# led1.net
KiCad netlist of a schematic drawn in Altium Designer
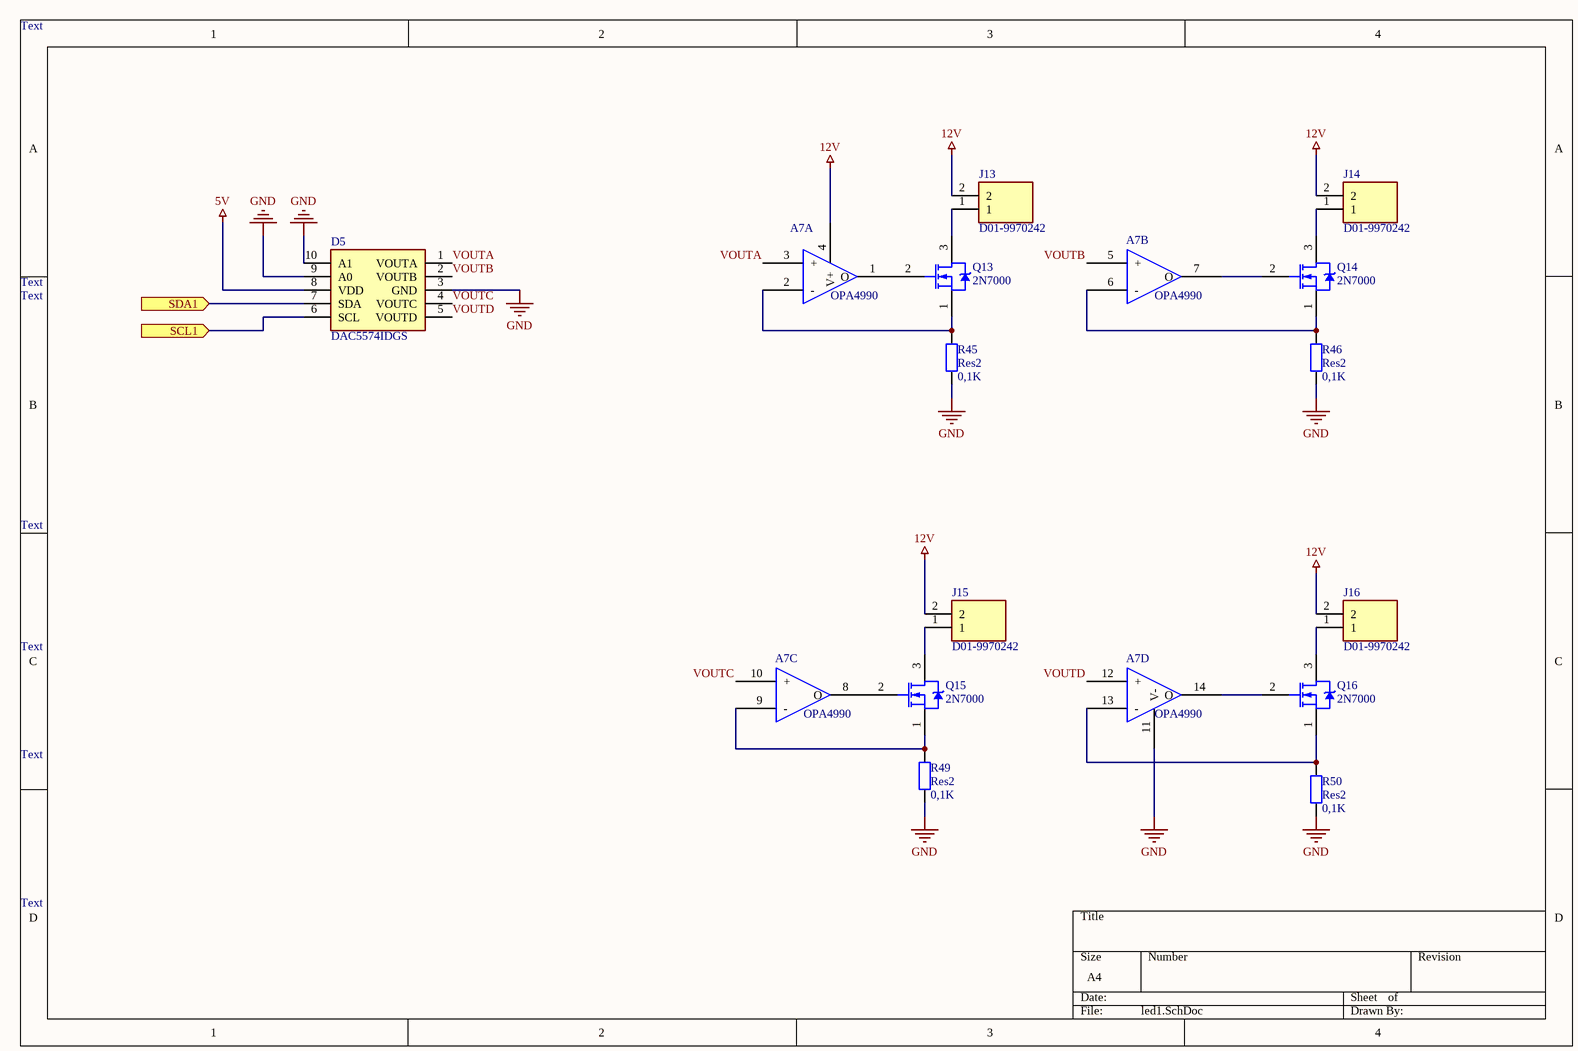
[diagram p0: led1.SchDoc]

(export (version "E")
  (design (tool "Eeschema 10.0.6"))
  (components
    (comp (ref "A7")
      (value "OPA4990")
      (footprint "SOIC127P600X175-14N")
      (libsource (lib "Kalibracija") (part "OPA4990"))
    )
    (comp (ref "D5")
      (value "DAC5574IDGS")
      (footprint "SOP50P490X110-10N")
      (description "Integrated Circuit")
      (fields
        (field (name "MOUSER PART NUMBER") "595-DAC5574IDGS")
        (field (name "RS PART NUMBER") "6621533P")
      )
      (libsource (lib "*") (part "DAC5574IDGS"))
    )
    (comp (ref "J13")
      (value "D01-9970242")
      (footprint "HDR1X2")
      (description "Connector")
      (fields (field (name "MOUSER PART NUMBER") "855-D01-9970242"))
      (libsource (lib "SamacSys2") (part "D01-9970242"))
    )
    (comp (ref "J14")
      (value "D01-9970242")
      (footprint "HDR1X2")
      (description "Connector")
      (fields (field (name "MOUSER PART NUMBER") "855-D01-9970242"))
      (libsource (lib "SamacSys2") (part "D01-9970242"))
    )
    (comp (ref "J15")
      (value "D01-9970242")
      (footprint "HDR1X2")
      (description "Connector")
      (fields (field (name "MOUSER PART NUMBER") "855-D01-9970242"))
      (libsource (lib "SamacSys2") (part "D01-9970242"))
    )
    (comp (ref "J16")
      (value "D01-9970242")
      (footprint "HDR1X2")
      (description "Connector")
      (fields (field (name "MOUSER PART NUMBER") "855-D01-9970242"))
      (libsource (lib "SamacSys2") (part "D01-9970242"))
    )
    (comp (ref "Q13")
      (value "2N7000")
      (footprint "ONSC-TO-92-3-29-11")
      (description "Small Signal MOSFET, 200 mA, 60 V, N-Channel, 3-Pin TO-92, Bulk Box")
      (fields (field (name "MANUFACTURER") "On Semiconductor"))
      (libsource (lib "Components - 24.04.20 - 07.58") (part "CMP-1058-00936-1"))
    )
    (comp (ref "Q14")
      (value "2N7000")
      (footprint "ONSC-TO-92-3-29-11")
      (description "Small Signal MOSFET, 200 mA, 60 V, N-Channel, 3-Pin TO-92, Bulk Box")
      (fields (field (name "MANUFACTURER") "On Semiconductor"))
      (libsource (lib "Components - 24.04.20 - 07.58") (part "CMP-1058-00936-1"))
    )
    (comp (ref "Q15")
      (value "2N7000")
      (footprint "ONSC-TO-92-3-29-11")
      (description "Small Signal MOSFET, 200 mA, 60 V, N-Channel, 3-Pin TO-92, Bulk Box")
      (fields (field (name "MANUFACTURER") "On Semiconductor"))
      (libsource (lib "Components - 24.04.20 - 07.58") (part "CMP-1058-00936-1"))
    )
    (comp (ref "Q16")
      (value "2N7000")
      (footprint "ONSC-TO-92-3-29-11")
      (description "Small Signal MOSFET, 200 mA, 60 V, N-Channel, 3-Pin TO-92, Bulk Box")
      (fields (field (name "MANUFACTURER") "On Semiconductor"))
      (libsource (lib "Components - 24.04.20 - 07.58") (part "CMP-1058-00936-1"))
    )
    (comp (ref "R45")
      (value "Res2")
      (footprint "C1210")
      (description "Resistor")
      (fields (field (name "ALTIUM_VALUE") "0,1K") (field (name "PUBLISHER") "Altium Limited"))
      (libsource (lib "Miscellaneous Devices") (part "Res2"))
    )
    (comp (ref "R46")
      (value "Res2")
      (footprint "C1210")
      (description "Resistor")
      (fields (field (name "ALTIUM_VALUE") "0,1K") (field (name "PUBLISHER") "Altium Limited"))
      (libsource (lib "Miscellaneous Devices") (part "Res2"))
    )
    (comp (ref "R49")
      (value "Res2")
      (footprint "C1210")
      (description "Resistor")
      (fields (field (name "ALTIUM_VALUE") "0,1K") (field (name "PUBLISHER") "Altium Limited"))
      (libsource (lib "") (part "Res2_1"))
    )
    (comp (ref "R50")
      (value "Res2")
      (footprint "C1210")
      (description "Resistor")
      (fields (field (name "ALTIUM_VALUE") "0,1K") (field (name "PUBLISHER") "Altium Limited"))
      (libsource (lib "") (part "Res2_1"))
    )
  )
  (nets
    (net (code "1") (name "/SCL1") (class "Default")
      (node (ref "D5") (pin "6") (pinfunction "SCL_6") (pintype "passive"))
    )
    (net (code "2") (name "/SDA1") (class "Default")
      (node (ref "D5") (pin "7") (pinfunction "SDA_7") (pintype "passive"))
    )
    (net (code "3") (name "/VOUTA") (class "Default")
      (node (ref "A7") (pin "3") (pinfunction "+_3") (pintype "passive"))
      (node (ref "D5") (pin "1") (pinfunction "VOUTA_1") (pintype "passive"))
    )
    (net (code "4") (name "/VOUTB") (class "Default")
      (node (ref "A7") (pin "5") (pinfunction "+_5") (pintype "passive"))
      (node (ref "D5") (pin "2") (pinfunction "VOUTB_2") (pintype "passive"))
    )
    (net (code "5") (name "/VOUTC") (class "Default")
      (node (ref "A7") (pin "10") (pinfunction "+_10") (pintype "passive"))
      (node (ref "D5") (pin "4") (pinfunction "VOUTC_4") (pintype "passive"))
    )
    (net (code "6") (name "/VOUTD") (class "Default")
      (node (ref "A7") (pin "12") (pinfunction "+_12") (pintype "passive"))
      (node (ref "D5") (pin "5") (pinfunction "VOUTD_5") (pintype "passive"))
    )
    (net (code "7") (name "5V") (class "Default")
      (node (ref "D5") (pin "8") (pinfunction "VDD_8") (pintype "passive"))
    )
    (net (code "8") (name "12V") (class "Default")
      (node (ref "A7") (pin "4") (pinfunction "V+_4") (pintype "power_in"))
      (node (ref "J13") (pin "2") (pinfunction "2_2") (pintype "passive"))
      (node (ref "J14") (pin "2") (pinfunction "2_2") (pintype "passive"))
      (node (ref "J15") (pin "2") (pinfunction "2_2") (pintype "passive"))
      (node (ref "J16") (pin "2") (pinfunction "2_2") (pintype "passive"))
    )
    (net (code "9") (name "GND") (class "Default")
      (node (ref "A7") (pin "11") (pinfunction "V-_11") (pintype "power_in"))
      (node (ref "D5") (pin "10") (pinfunction "A1_10") (pintype "passive"))
      (node (ref "D5") (pin "3") (pinfunction "GND_3") (pintype "passive"))
      (node (ref "D5") (pin "9") (pinfunction "A0_9") (pintype "passive"))
      (node (ref "R45") (pin "1") (pinfunction "1_1") (pintype "passive"))
      (node (ref "R46") (pin "1") (pinfunction "1_1") (pintype "passive"))
      (node (ref "R49") (pin "2") (pinfunction "2_2") (pintype "passive"))
      (node (ref "R50") (pin "2") (pinfunction "2_2") (pintype "passive"))
    )
    (net (code "10") (name "Net-(A7A--)") (class "Default")
      (node (ref "A7") (pin "2") (pinfunction "-_2") (pintype "passive"))
      (node (ref "Q13") (pin "1") (pinfunction "S_1") (pintype "passive"))
      (node (ref "R45") (pin "2") (pinfunction "2_2") (pintype "passive"))
    )
    (net (code "11") (name "Net-(A7A-O)") (class "Default")
      (node (ref "A7") (pin "1") (pinfunction "O_1") (pintype "passive"))
      (node (ref "Q13") (pin "2") (pinfunction "G_2") (pintype "passive"))
    )
    (net (code "12") (name "Net-(A7B--)") (class "Default")
      (node (ref "A7") (pin "6") (pinfunction "-_6") (pintype "passive"))
      (node (ref "Q14") (pin "1") (pinfunction "S_1") (pintype "passive"))
      (node (ref "R46") (pin "2") (pinfunction "2_2") (pintype "passive"))
    )
    (net (code "13") (name "Net-(A7B-O)") (class "Default")
      (node (ref "A7") (pin "7") (pinfunction "O_7") (pintype "passive"))
      (node (ref "Q14") (pin "2") (pinfunction "G_2") (pintype "passive"))
    )
    (net (code "14") (name "Net-(A7C--)") (class "Default")
      (node (ref "A7") (pin "9") (pinfunction "-_9") (pintype "passive"))
      (node (ref "Q15") (pin "1") (pinfunction "S_1") (pintype "passive"))
      (node (ref "R49") (pin "1") (pinfunction "1_1") (pintype "passive"))
    )
    (net (code "15") (name "Net-(A7C-O)") (class "Default")
      (node (ref "A7") (pin "8") (pinfunction "O_8") (pintype "passive"))
      (node (ref "Q15") (pin "2") (pinfunction "G_2") (pintype "passive"))
    )
    (net (code "16") (name "Net-(A7D--)") (class "Default")
      (node (ref "A7") (pin "13") (pinfunction "-_13") (pintype "passive"))
      (node (ref "Q16") (pin "1") (pinfunction "S_1") (pintype "passive"))
      (node (ref "R50") (pin "1") (pinfunction "1_1") (pintype "passive"))
    )
    (net (code "17") (name "Net-(A7D-O)") (class "Default")
      (node (ref "A7") (pin "14") (pinfunction "O_14") (pintype "passive"))
      (node (ref "Q16") (pin "2") (pinfunction "G_2") (pintype "passive"))
    )
    (net (code "18") (name "Net-(Q13-D)") (class "Default")
      (node (ref "J13") (pin "1") (pinfunction "1_1") (pintype "passive"))
      (node (ref "Q13") (pin "3") (pinfunction "D_3") (pintype "passive"))
    )
    (net (code "19") (name "Net-(Q14-D)") (class "Default")
      (node (ref "J14") (pin "1") (pinfunction "1_1") (pintype "passive"))
      (node (ref "Q14") (pin "3") (pinfunction "D_3") (pintype "passive"))
    )
    (net (code "20") (name "Net-(Q15-D)") (class "Default")
      (node (ref "J15") (pin "1") (pinfunction "1_1") (pintype "passive"))
      (node (ref "Q15") (pin "3") (pinfunction "D_3") (pintype "passive"))
    )
    (net (code "21") (name "Net-(Q16-D)") (class "Default")
      (node (ref "J16") (pin "1") (pinfunction "1_1") (pintype "passive"))
      (node (ref "Q16") (pin "3") (pinfunction "D_3") (pintype "passive"))
    )
  )
)
